# EVSE.net
KiCad netlist of a schematic drawn in EAGLE
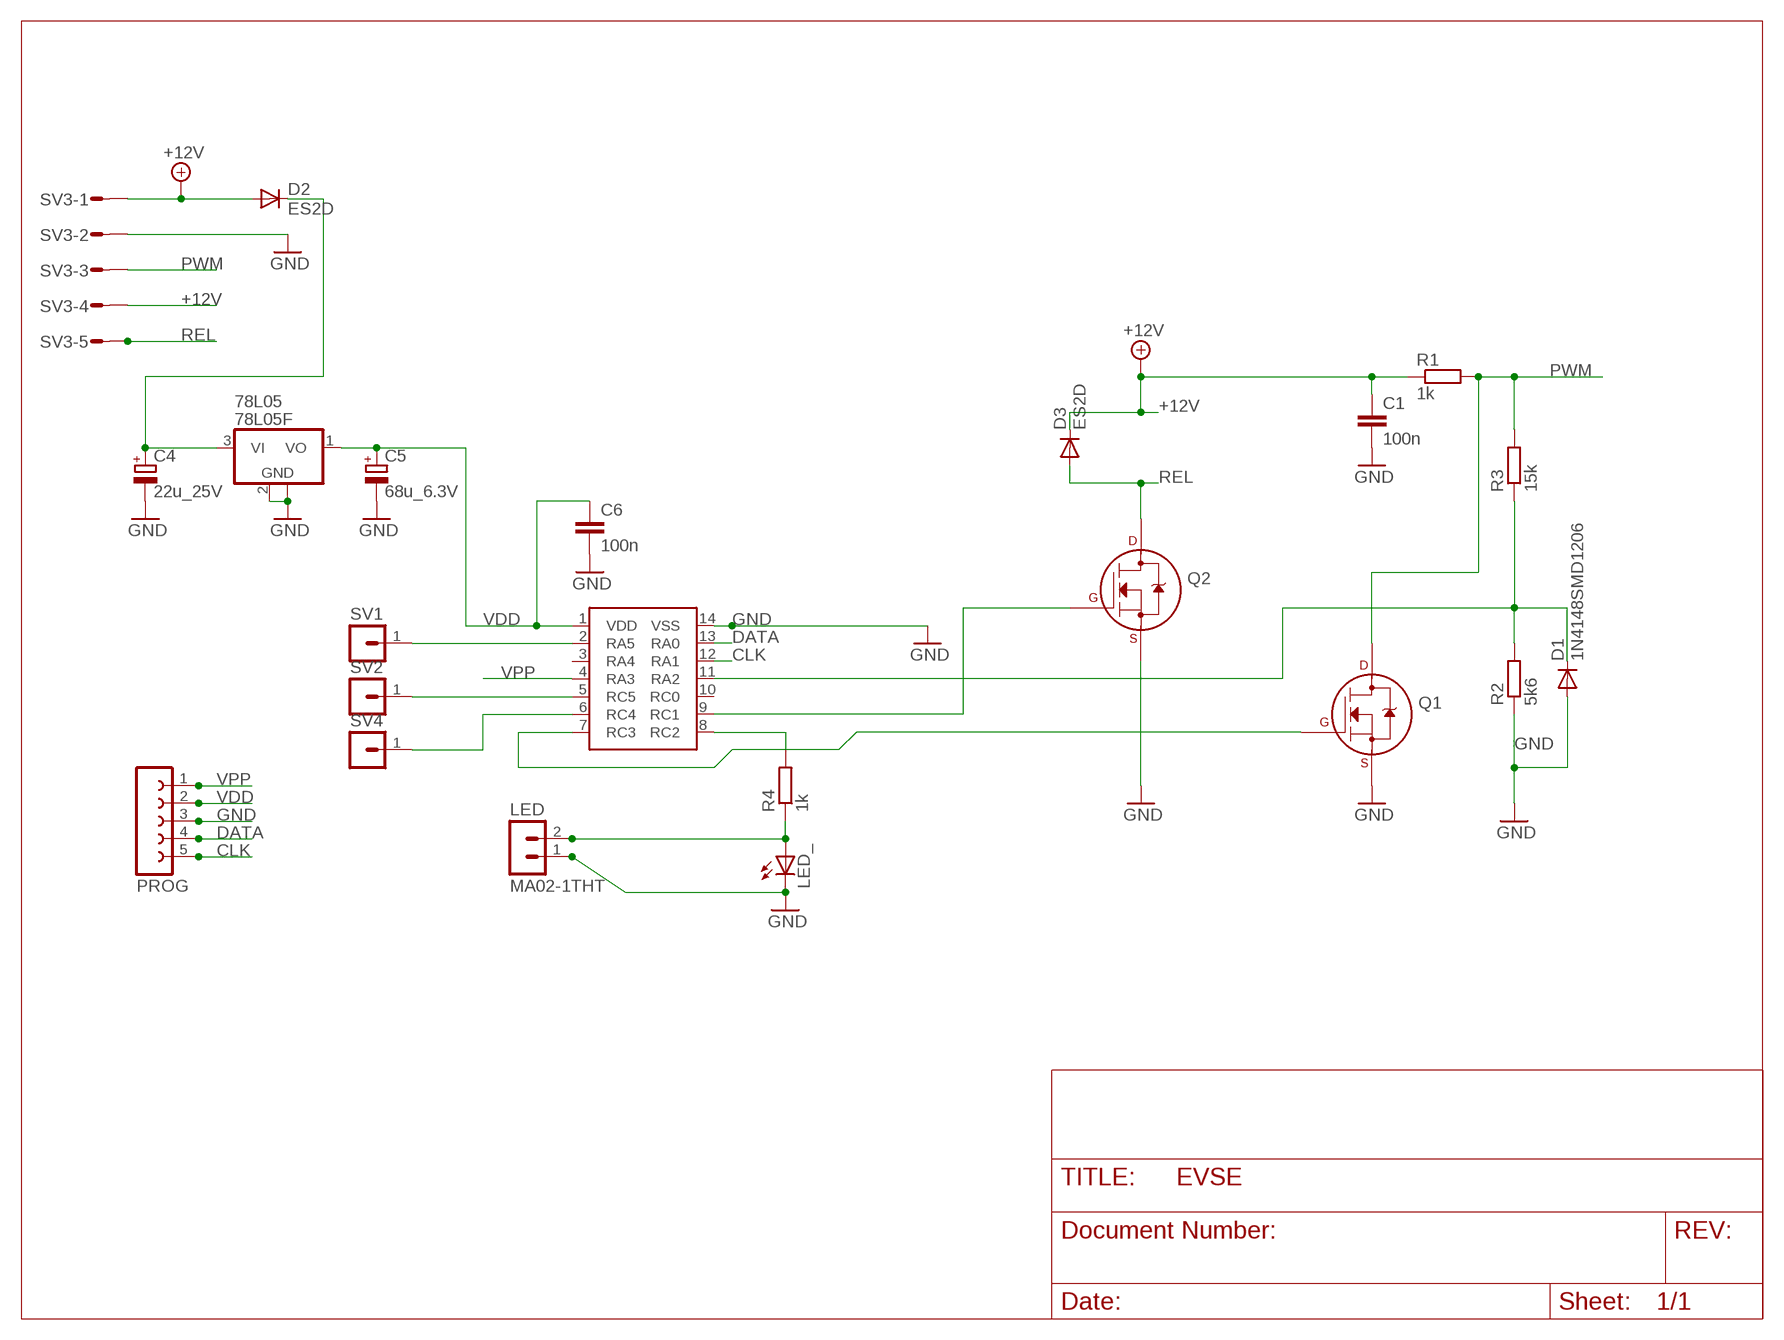
[diagram p0: schematic, sheet 1]

(export (version "E")
  (design (tool "Eeschema 10.0.6"))
  (components
    (comp (ref "78L05")
      (value "78L05F")
      (footprint "eagle-import:SOT89")
      (libsource (lib "eagle-import") (part "78LF05"))
    )
    (comp (ref "C1")
      (value "100n")
      (footprint "eagle-import:C0805")
      (libsource (lib "eagle-import") (part "C-EUC0805"))
    )
    (comp (ref "C4")
      (value "22u_25V")
      (footprint "eagle-import:B_3528-21W")
      (libsource (lib "eagle-import") (part "CPOL-EUB/3528-21W"))
    )
    (comp (ref "C5")
      (value "68u_6.3V")
      (footprint "eagle-import:B_3528-21W")
      (libsource (lib "eagle-import") (part "CPOL-EUB/3528-21W"))
    )
    (comp (ref "C6")
      (value "100n")
      (footprint "eagle-import:C0805")
      (libsource (lib "eagle-import") (part "C-EUC0805"))
    )
    (comp (ref "D1")
      (value "1N4148SMD1206")
      (footprint "eagle-import:D1206")
      (libsource (lib "eagle-import") (part "1N4148SMD1206"))
    )
    (comp (ref "D2")
      (value "ES2D")
      (footprint "eagle-import:SMB")
      (libsource (lib "eagle-import") (part "ES2D"))
    )
    (comp (ref "D3")
      (value "ES2D")
      (footprint "eagle-import:SMB")
      (libsource (lib "eagle-import") (part "ES2D"))
    )
    (comp (ref "LED")
      (value "MA02-1THT")
      (footprint "eagle-import:MA02-1")
      (libsource (lib "eagle-import") (part "MA02-1THT"))
    )
    (comp (ref "LED_")
      (value "LEDSMT1206")
      (footprint "eagle-import:1206")
      (libsource (lib "eagle-import") (part "LEDSMT1206"))
    )
    (comp (ref "PIC16F1825")
      (value "PIC16F1825SOIC")
      (footprint "eagle-import:SO-14")
      (libsource (lib "eagle-import") (part "PIC16F1825SOIC"))
    )
    (comp (ref "PROG")
      (value "FE05-1")
      (footprint "eagle-import:FE05-1")
      (libsource (lib "eagle-import") (part "FE05-1"))
    )
    (comp (ref "Q1")
      (value "2N7002_SOT23")
      (footprint "eagle-import:SOT-23")
      (libsource (lib "eagle-import") (part "2N700_SOT232"))
    )
    (comp (ref "Q2")
      (value "2N7002_SOT23")
      (footprint "eagle-import:SOT-23")
      (libsource (lib "eagle-import") (part "2N700_SOT232"))
    )
    (comp (ref "R1")
      (value "1k")
      (footprint "eagle-import:R0805")
      (libsource (lib "eagle-import") (part "R-EU_R0805"))
    )
    (comp (ref "R2")
      (value "5k6")
      (footprint "eagle-import:R0805")
      (libsource (lib "eagle-import") (part "R-EU_R0805"))
    )
    (comp (ref "R3")
      (value "15k")
      (footprint "eagle-import:R0805")
      (libsource (lib "eagle-import") (part "R-EU_R0805"))
    )
    (comp (ref "R4")
      (value "1k")
      (footprint "eagle-import:R0805")
      (libsource (lib "eagle-import") (part "R-EU_R0805"))
    )
    (comp (ref "SV1")
      (value "PIN-HEADER1")
      (footprint "eagle-import:PIN-HEADER1")
      (libsource (lib "eagle-import") (part "PIN-HEADER1"))
    )
    (comp (ref "SV2")
      (value "PIN-HEADER1")
      (footprint "eagle-import:PIN-HEADER1")
      (libsource (lib "eagle-import") (part "PIN-HEADER1"))
    )
    (comp (ref "SV3")
      (value "MT6-5")
      (footprint "eagle-import:MT6-5")
      (libsource (lib "eagle-import") (part "MT6-5"))
    )
    (comp (ref "SV4")
      (value "PIN-HEADER1")
      (footprint "eagle-import:PIN-HEADER1")
      (libsource (lib "eagle-import") (part "PIN-HEADER1"))
    )
  )
  (nets
    (net (code "1") (name "+12V") (class "Default")
      (node (ref "C1") (pin "1") (pinfunction "1_1") (pintype "passive"))
      (node (ref "D2") (pin "A") (pinfunction "A_A") (pintype "passive"))
      (node (ref "D3") (pin "C") (pinfunction "C_C") (pintype "passive"))
      (node (ref "R1") (pin "1") (pinfunction "1_1") (pintype "passive"))
      (node (ref "SV3") (pin "1") (pinfunction "S_1") (pintype "passive"))
      (node (ref "SV3") (pin "4") (pinfunction "S_4") (pintype "passive"))
    )
    (net (code "2") (name "/CLK") (class "Default")
      (node (ref "PIC16F1825") (pin "12") (pinfunction "RA1_12") (pintype "bidirectional"))
      (node (ref "PROG") (pin "5") (pinfunction "5_5") (pintype "passive"))
    )
    (net (code "3") (name "/DATA") (class "Default")
      (node (ref "PIC16F1825") (pin "13") (pinfunction "RA0_13") (pintype "bidirectional"))
      (node (ref "PROG") (pin "4") (pinfunction "4_4") (pintype "passive"))
    )
    (net (code "4") (name "/PWM") (class "Default")
      (node (ref "Q1") (pin "3") (pinfunction "D_3") (pintype "bidirectional"))
      (node (ref "R1") (pin "2") (pinfunction "2_2") (pintype "passive"))
      (node (ref "R3") (pin "2") (pinfunction "2_2") (pintype "passive"))
      (node (ref "SV3") (pin "3") (pinfunction "S_3") (pintype "passive"))
    )
    (net (code "5") (name "/REL") (class "Default")
      (node (ref "D3") (pin "A") (pinfunction "A_A") (pintype "passive"))
      (node (ref "Q2") (pin "3") (pinfunction "D_3") (pintype "bidirectional"))
      (node (ref "SV3") (pin "5") (pinfunction "S_5") (pintype "passive"))
    )
    (net (code "6") (name "/VDD") (class "Default")
      (node (ref "78L05") (pin "1") (pinfunction "VO_1") (pintype "passive"))
      (node (ref "C5") (pin "+") (pinfunction "+_+") (pintype "passive"))
      (node (ref "C6") (pin "1") (pinfunction "1_1") (pintype "passive"))
      (node (ref "PIC16F1825") (pin "1") (pinfunction "VDD_1") (pintype "power_in"))
      (node (ref "PROG") (pin "2") (pinfunction "2_2") (pintype "passive"))
    )
    (net (code "7") (name "/VPP") (class "Default")
      (node (ref "PIC16F1825") (pin "4") (pinfunction "RA3_4") (pintype "input"))
      (node (ref "PROG") (pin "1") (pinfunction "1_1") (pintype "passive"))
    )
    (net (code "8") (name "GND") (class "Default")
      (node (ref "78L05") (pin "2") (pinfunction "GND_2") (pintype "passive"))
      (node (ref "78L05") (pin "2@1") (pinfunction "GND_2@1") (pintype "passive"))
      (node (ref "C1") (pin "2") (pinfunction "2_2") (pintype "passive"))
      (node (ref "C4") (pin "-") (pinfunction "-_-") (pintype "passive"))
      (node (ref "C5") (pin "-") (pinfunction "-_-") (pintype "passive"))
      (node (ref "C6") (pin "2") (pinfunction "2_2") (pintype "passive"))
      (node (ref "D1") (pin "A") (pinfunction "A_A") (pintype "passive"))
      (node (ref "LED") (pin "1") (pinfunction "1_1") (pintype "passive"))
      (node (ref "LED_") (pin "C") (pinfunction "C_C") (pintype "passive"))
      (node (ref "PIC16F1825") (pin "14") (pinfunction "VSS_14") (pintype "power_in"))
      (node (ref "PROG") (pin "3") (pinfunction "3_3") (pintype "passive"))
      (node (ref "Q1") (pin "2") (pinfunction "S_2") (pintype "bidirectional"))
      (node (ref "Q2") (pin "2") (pinfunction "S_2") (pintype "bidirectional"))
      (node (ref "R2") (pin "1") (pinfunction "1_1") (pintype "passive"))
      (node (ref "SV3") (pin "2") (pinfunction "S_2") (pintype "passive"))
    )
    (net (code "9") (name "Net-(78L05-VI)") (class "Default")
      (node (ref "78L05") (pin "3") (pinfunction "VI_3") (pintype "input"))
      (node (ref "C4") (pin "+") (pinfunction "+_+") (pintype "passive"))
      (node (ref "D2") (pin "C") (pinfunction "C_C") (pintype "passive"))
    )
    (net (code "10") (name "Net-(LED-Pad2)") (class "Default")
      (node (ref "LED") (pin "2") (pinfunction "2_2") (pintype "passive"))
      (node (ref "LED_") (pin "A") (pinfunction "A_A") (pintype "passive"))
      (node (ref "R4") (pin "1") (pinfunction "1_1") (pintype "passive"))
    )
    (net (code "11") (name "Net-(PIC16F1825-RA2)") (class "Default")
      (node (ref "D1") (pin "C") (pinfunction "C_C") (pintype "passive"))
      (node (ref "PIC16F1825") (pin "11") (pinfunction "RA2_11") (pintype "bidirectional"))
      (node (ref "R2") (pin "2") (pinfunction "2_2") (pintype "passive"))
      (node (ref "R3") (pin "1") (pinfunction "1_1") (pintype "passive"))
    )
    (net (code "12") (name "Net-(PIC16F1825-RA5)") (class "Default")
      (node (ref "PIC16F1825") (pin "2") (pinfunction "RA5_2") (pintype "bidirectional"))
      (node (ref "SV1") (pin "1") (pinfunction "3_1") (pintype "passive"))
    )
    (net (code "13") (name "Net-(PIC16F1825-RC1)") (class "Default")
      (node (ref "PIC16F1825") (pin "9") (pinfunction "RC1_9") (pintype "bidirectional"))
      (node (ref "Q2") (pin "1") (pinfunction "G_1") (pintype "tri_state"))
    )
    (net (code "14") (name "Net-(PIC16F1825-RC2)") (class "Default")
      (node (ref "PIC16F1825") (pin "8") (pinfunction "RC2_8") (pintype "bidirectional"))
      (node (ref "R4") (pin "2") (pinfunction "2_2") (pintype "passive"))
    )
    (net (code "15") (name "Net-(PIC16F1825-RC3)") (class "Default")
      (node (ref "PIC16F1825") (pin "7") (pinfunction "RC3_7") (pintype "bidirectional"))
      (node (ref "Q1") (pin "1") (pinfunction "G_1") (pintype "tri_state"))
    )
    (net (code "16") (name "Net-(PIC16F1825-RC4)") (class "Default")
      (node (ref "PIC16F1825") (pin "6") (pinfunction "RC4_6") (pintype "bidirectional"))
      (node (ref "SV4") (pin "1") (pinfunction "3_1") (pintype "passive"))
    )
    (net (code "17") (name "Net-(PIC16F1825-RC5)") (class "Default")
      (node (ref "PIC16F1825") (pin "5") (pinfunction "RC5_5") (pintype "bidirectional"))
      (node (ref "SV2") (pin "1") (pinfunction "3_1") (pintype "passive"))
    )
    (net (code "18") (name "unconnected-(PIC16F1825-RA4-Pad3)") (class "Default")
      (node (ref "PIC16F1825") (pin "3") (pinfunction "RA4_3") (pintype "bidirectional"))
    )
    (net (code "19") (name "unconnected-(PIC16F1825-RC0-Pad10)") (class "Default")
      (node (ref "PIC16F1825") (pin "10") (pinfunction "RC0_10") (pintype "bidirectional"))
    )
  )
)
